# MainBoardR6.net
KiCad netlist of a schematic drawn in EAGLE
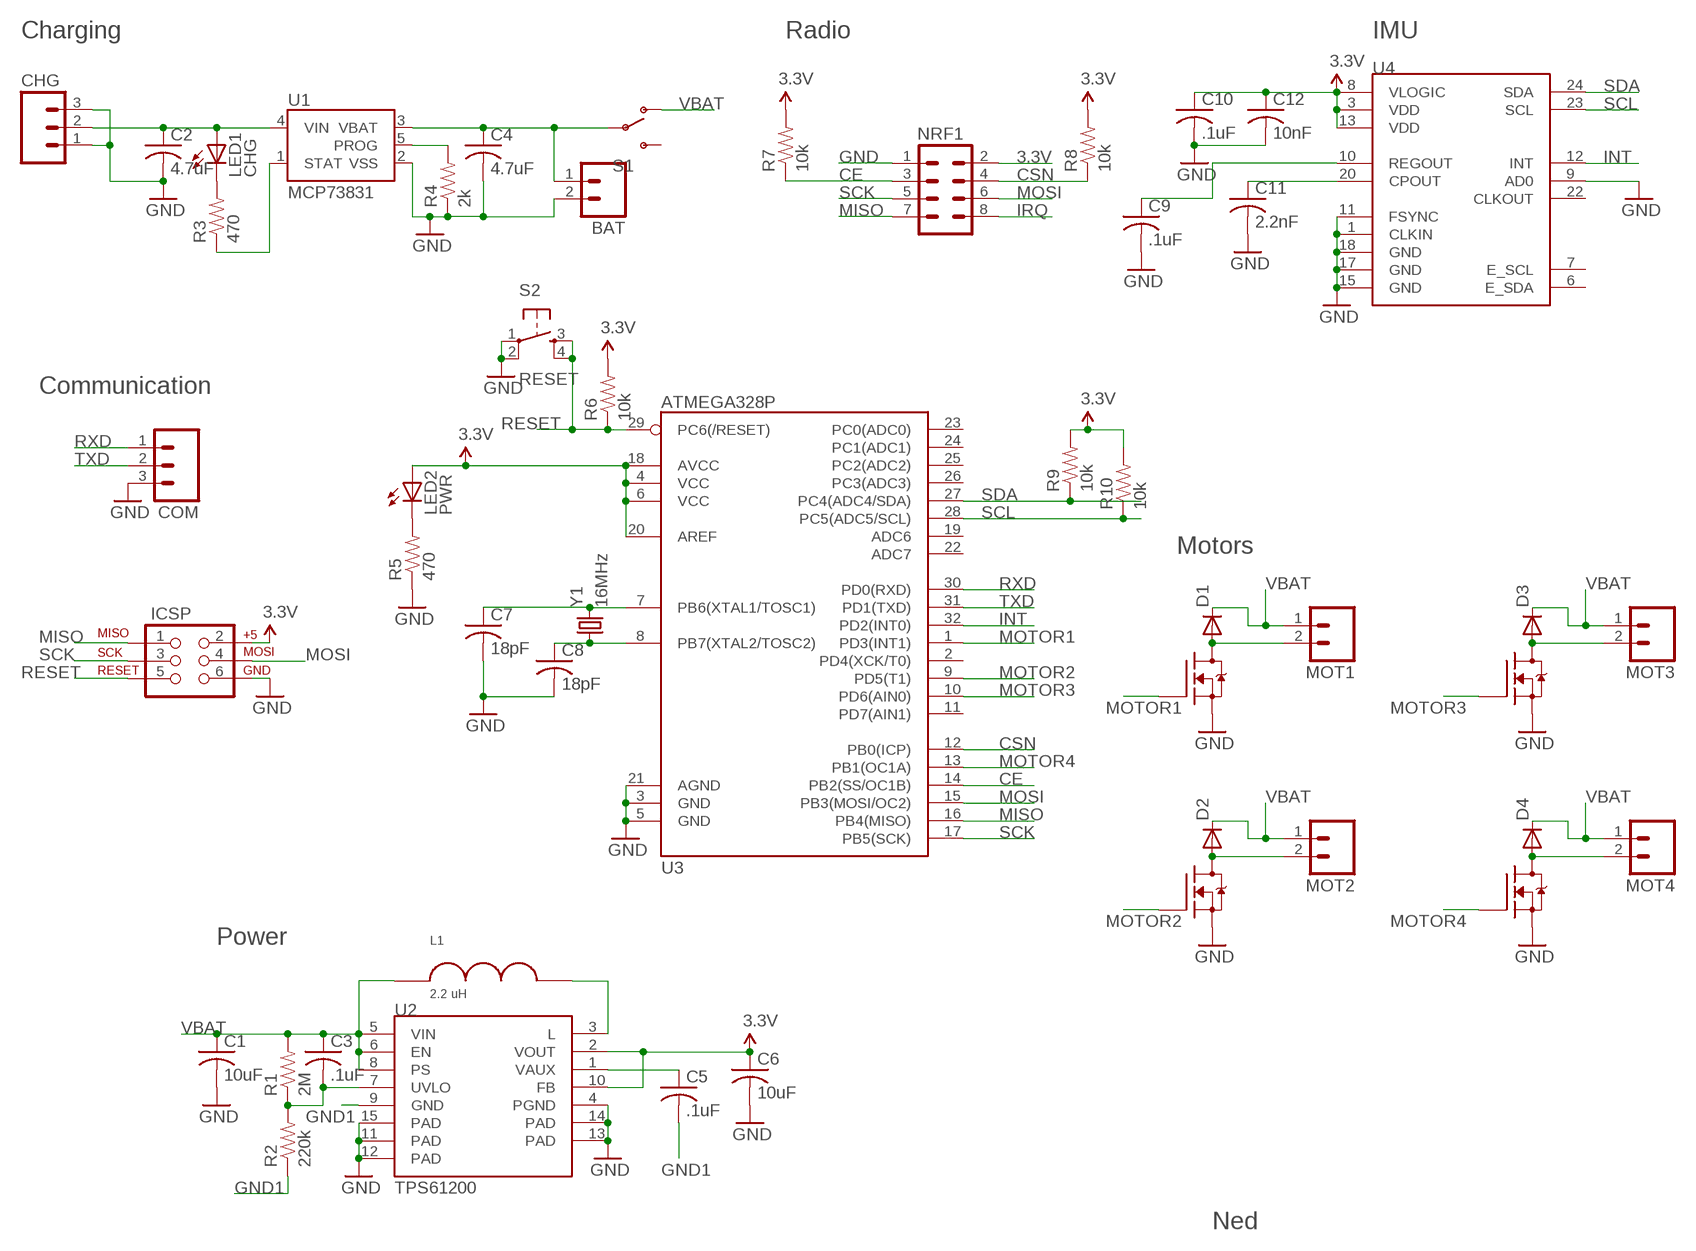
[diagram p0: schematic, sheet 1]

(export (version "E")
  (design (tool "Eeschema 10.0.6"))
  (components
    (comp (ref "BAT")
      (value "M02LOCK_LONGPADS")
      (footprint "eagle-import:1X02_LOCK_LONGPADS")
      (libsource (lib "eagle-import") (part "M02LOCK_LONGPADS"))
    )
    (comp (ref "C1")
      (value "10uF")
      (footprint "eagle-import:C0805")
      (libsource (lib "eagle-import") (part "C-USC0805"))
    )
    (comp (ref "C2")
      (value "4.7uF")
      (footprint "eagle-import:C0805")
      (libsource (lib "eagle-import") (part "C-USC0805"))
    )
    (comp (ref "C3")
      (value ".1uF")
      (footprint "eagle-import:C0805")
      (libsource (lib "eagle-import") (part "C-USC0805"))
    )
    (comp (ref "C4")
      (value "4.7uF")
      (footprint "eagle-import:C0805")
      (libsource (lib "eagle-import") (part "C-USC0805"))
    )
    (comp (ref "C5")
      (value ".1uF")
      (footprint "eagle-import:C0805")
      (libsource (lib "eagle-import") (part "C-USC0805"))
    )
    (comp (ref "C6")
      (value "10uF")
      (footprint "eagle-import:C0805")
      (libsource (lib "eagle-import") (part "C-USC0805"))
    )
    (comp (ref "C7")
      (value "18pF")
      (footprint "eagle-import:C0805")
      (libsource (lib "eagle-import") (part "C-USC0805"))
    )
    (comp (ref "C8")
      (value "18pF")
      (footprint "eagle-import:C0805")
      (libsource (lib "eagle-import") (part "C-USC0805"))
    )
    (comp (ref "C9")
      (value ".1uF")
      (footprint "eagle-import:C0805")
      (libsource (lib "eagle-import") (part "C-USC0805"))
    )
    (comp (ref "C10")
      (value ".1uF")
      (footprint "eagle-import:C0805")
      (libsource (lib "eagle-import") (part "C-USC0805"))
    )
    (comp (ref "C11")
      (value "2.2nF")
      (footprint "eagle-import:C0805")
      (libsource (lib "eagle-import") (part "C-USC0805"))
    )
    (comp (ref "C12")
      (value "10nF")
      (footprint "eagle-import:C0805")
      (libsource (lib "eagle-import") (part "C-USC0805"))
    )
    (comp (ref "CHG")
      (value "M03LONGPADS")
      (footprint "eagle-import:1X03_LONGPADS")
      (libsource (lib "eagle-import") (part "M03LONGPADS"))
    )
    (comp (ref "COM")
      (value "M03LONGPADS")
      (footprint "eagle-import:1X03_LONGPADS")
      (libsource (lib "eagle-import") (part "M03LONGPADS"))
    )
    (comp (ref "D1")
      (value "BAS16-V-GS18")
      (footprint "eagle-import:SOT23")
      (libsource (lib "eagle-import") (part "BAS16-V-GS18"))
    )
    (comp (ref "D2")
      (value "BAS16-V-GS18")
      (footprint "eagle-import:SOT23")
      (libsource (lib "eagle-import") (part "BAS16-V-GS18"))
    )
    (comp (ref "D3")
      (value "BAS16-V-GS18")
      (footprint "eagle-import:SOT23")
      (libsource (lib "eagle-import") (part "BAS16-V-GS18"))
    )
    (comp (ref "D4")
      (value "BAS16-V-GS18")
      (footprint "eagle-import:SOT23")
      (libsource (lib "eagle-import") (part "BAS16-V-GS18"))
    )
    (comp (ref "ICSP")
      (value "AVR_SPI_PRG_62X3_LOCK")
      (footprint "eagle-import:2X3_LOCK")
      (libsource (lib "eagle-import") (part "AVR_SPI_PRG_62X3_LOCK"))
    )
    (comp (ref "L1")
      (value "2.2 uH")
      (footprint "eagle-import:2518")
      (libsource (lib "eagle-import") (part "BRHL2518T2R2M"))
    )
    (comp (ref "LED1")
      (value "CHG")
      (footprint "eagle-import:LED-1206")
      (libsource (lib "eagle-import") (part "LED1206"))
    )
    (comp (ref "LED2")
      (value "PWR")
      (footprint "eagle-import:LED-1206")
      (libsource (lib "eagle-import") (part "LED1206"))
    )
    (comp (ref "MOT1")
      (value "M02LOCK_LONGPADS")
      (footprint "eagle-import:1X02_LOCK_LONGPADS")
      (libsource (lib "eagle-import") (part "M02LOCK_LONGPADS"))
    )
    (comp (ref "MOT2")
      (value "M02LOCK_LONGPADS")
      (footprint "eagle-import:1X02_LOCK_LONGPADS")
      (libsource (lib "eagle-import") (part "M02LOCK_LONGPADS"))
    )
    (comp (ref "MOT3")
      (value "M02LOCK_LONGPADS")
      (footprint "eagle-import:1X02_LOCK_LONGPADS")
      (libsource (lib "eagle-import") (part "M02LOCK_LONGPADS"))
    )
    (comp (ref "MOT4")
      (value "M02LOCK_LONGPADS")
      (footprint "eagle-import:1X02_LOCK_LONGPADS")
      (libsource (lib "eagle-import") (part "M02LOCK_LONGPADS"))
    )
    (comp (ref "NRF1")
      (value "M04X2")
      (footprint "eagle-import:2X4")
      (libsource (lib "eagle-import") (part "M04X2"))
    )
    (comp (ref "R1")
      (value "2M")
      (footprint "eagle-import:0805")
      (libsource (lib "eagle-import") (part "RESISTOR0805-RES"))
    )
    (comp (ref "R2")
      (value "220k")
      (footprint "eagle-import:0805")
      (libsource (lib "eagle-import") (part "RESISTOR0805-RES"))
    )
    (comp (ref "R3")
      (value "470")
      (footprint "eagle-import:0805")
      (libsource (lib "eagle-import") (part "RESISTOR0805-RES"))
    )
    (comp (ref "R4")
      (value "2k")
      (footprint "eagle-import:0805")
      (libsource (lib "eagle-import") (part "RESISTOR0805-RES"))
    )
    (comp (ref "R5")
      (value "470")
      (footprint "eagle-import:0805")
      (libsource (lib "eagle-import") (part "RESISTOR0805-RES"))
    )
    (comp (ref "R6")
      (value "10k")
      (footprint "eagle-import:0805")
      (libsource (lib "eagle-import") (part "RESISTOR0805-RES"))
    )
    (comp (ref "R7")
      (value "10k")
      (footprint "eagle-import:0805")
      (libsource (lib "eagle-import") (part "RESISTOR0805-RES"))
    )
    (comp (ref "R8")
      (value "10k")
      (footprint "eagle-import:0805")
      (libsource (lib "eagle-import") (part "RESISTOR0805-RES"))
    )
    (comp (ref "R9")
      (value "10k")
      (footprint "eagle-import:0805")
      (libsource (lib "eagle-import") (part "RESISTOR0805-RES"))
    )
    (comp (ref "R10")
      (value "10k")
      (footprint "eagle-import:0805")
      (libsource (lib "eagle-import") (part "RESISTOR0805-RES"))
    )
    (comp (ref "S1")
      (value "SWITCH-SPST-SMD-A")
      (footprint "eagle-import:SWITCH-SPST-SMD-A")
      (libsource (lib "eagle-import") (part "SWITCH-SPST-SMD-A"))
    )
    (comp (ref "S2")
      (value "RESET")
      (footprint "eagle-import:TACTILE_SWITCH_SMD")
      (libsource (lib "eagle-import") (part "TAC_SWITCHSMD"))
    )
    (comp (ref "T1")
      (value "SI1902CDL")
      (footprint "eagle-import:SOT363_INFINEON")
      (libsource (lib "eagle-import") (part "SI1902CDL"))
    )
    (comp (ref "T2")
      (value "SI1902CDL")
      (footprint "eagle-import:SOT363_INFINEON")
      (libsource (lib "eagle-import") (part "SI1902CDL"))
    )
    (comp (ref "U1")
      (value "MCP73831")
      (footprint "eagle-import:SOT23-5")
      (libsource (lib "eagle-import") (part "MCP73831"))
    )
    (comp (ref "U2")
      (value "TPS61200")
      (footprint "eagle-import:QFN-10_PAD")
      (libsource (lib "eagle-import") (part "TPS61200"))
    )
    (comp (ref "U3")
      (value "ATMEGA328P")
      (footprint "eagle-import:TQFP32-08")
      (libsource (lib "eagle-import") (part "ATMEGA328_SMT"))
    )
    (comp (ref "U4")
      (value "MPU-9150QFN-24-NP")
      (footprint "eagle-import:QFN-24-NP")
      (libsource (lib "eagle-import") (part "MPU-9150QFN-24-NP"))
    )
    (comp (ref "Y1")
      (value "16MHz")
      (footprint "eagle-import:CRYSTAL-SMD-5X3")
      (libsource (lib "eagle-import") (part "CRYSTAL5X3"))
    )
  )
  (nets
    (net (code "1") (name "/CE") (class "Default")
      (node (ref "NRF1") (pin "3") (pinfunction "3_3") (pintype "passive"))
      (node (ref "R7") (pin "1") (pinfunction "1_1") (pintype "passive"))
      (node (ref "U3") (pin "14") (pinfunction "PB2(SS/OC1B)_14") (pintype "bidirectional"))
    )
    (net (code "2") (name "/CSN") (class "Default")
      (node (ref "NRF1") (pin "4") (pinfunction "4_4") (pintype "passive"))
      (node (ref "R8") (pin "1") (pinfunction "1_1") (pintype "passive"))
      (node (ref "U3") (pin "12") (pinfunction "PB0(ICP)_12") (pintype "bidirectional"))
    )
    (net (code "3") (name "/GND1") (class "Default")
      (node (ref "C5") (pin "2") (pinfunction "2_2") (pintype "passive"))
      (node (ref "R2") (pin "1") (pinfunction "1_1") (pintype "passive"))
      (node (ref "U2") (pin "9") (pinfunction "GND_9") (pintype "power_in"))
    )
    (net (code "4") (name "/INT") (class "Default")
      (node (ref "U3") (pin "32") (pinfunction "PD2(INT0)_32") (pintype "bidirectional"))
      (node (ref "U4") (pin "12") (pinfunction "INT_12") (pintype "bidirectional"))
    )
    (net (code "5") (name "/IRQ") (class "Default")
      (node (ref "NRF1") (pin "8") (pinfunction "8_8") (pintype "passive"))
    )
    (net (code "6") (name "/MISO") (class "Default")
      (node (ref "ICSP") (pin "1") (pinfunction "1_1") (pintype "passive"))
      (node (ref "NRF1") (pin "7") (pinfunction "7_7") (pintype "passive"))
      (node (ref "U3") (pin "16") (pinfunction "PB4(MISO)_16") (pintype "bidirectional"))
    )
    (net (code "7") (name "/MOSI") (class "Default")
      (node (ref "ICSP") (pin "4") (pinfunction "4_4") (pintype "passive"))
      (node (ref "NRF1") (pin "6") (pinfunction "6_6") (pintype "passive"))
      (node (ref "U3") (pin "15") (pinfunction "PB3(MOSI/OC2)_15") (pintype "bidirectional"))
    )
    (net (code "8") (name "/MOTOR1") (class "Default")
      (node (ref "T1") (pin "2") (pinfunction "G_2") (pintype "passive"))
      (node (ref "U3") (pin "1") (pinfunction "PD3(INT1)_1") (pintype "bidirectional"))
    )
    (net (code "9") (name "/MOTOR2") (class "Default")
      (node (ref "T1") (pin "5") (pinfunction "G_5") (pintype "passive"))
      (node (ref "U3") (pin "9") (pinfunction "PD5(T1)_9") (pintype "bidirectional"))
    )
    (net (code "10") (name "/MOTOR3") (class "Default")
      (node (ref "T2") (pin "2") (pinfunction "G_2") (pintype "passive"))
      (node (ref "U3") (pin "10") (pinfunction "PD6(AIN0)_10") (pintype "bidirectional"))
    )
    (net (code "11") (name "/MOTOR4") (class "Default")
      (node (ref "T2") (pin "5") (pinfunction "G_5") (pintype "passive"))
      (node (ref "U3") (pin "13") (pinfunction "PB1(OC1A)_13") (pintype "bidirectional"))
    )
    (net (code "12") (name "/RESET") (class "Default")
      (node (ref "ICSP") (pin "5") (pinfunction "5_5") (pintype "passive"))
      (node (ref "R6") (pin "1") (pinfunction "1_1") (pintype "passive"))
      (node (ref "S2") (pin "3") (pinfunction "3_3") (pintype "passive"))
      (node (ref "S2") (pin "4") (pinfunction "4_4") (pintype "passive"))
      (node (ref "U3") (pin "29") (pinfunction "PC6(/RESET)_29") (pintype "bidirectional"))
    )
    (net (code "13") (name "/RXD") (class "Default")
      (node (ref "COM") (pin "1") (pinfunction "1_1") (pintype "passive"))
      (node (ref "U3") (pin "30") (pinfunction "PD0(RXD)_30") (pintype "bidirectional"))
    )
    (net (code "14") (name "/SCK") (class "Default")
      (node (ref "ICSP") (pin "3") (pinfunction "3_3") (pintype "passive"))
      (node (ref "NRF1") (pin "5") (pinfunction "5_5") (pintype "passive"))
      (node (ref "U3") (pin "17") (pinfunction "PB5(SCK)_17") (pintype "bidirectional"))
    )
    (net (code "15") (name "/SCL") (class "Default")
      (node (ref "R10") (pin "1") (pinfunction "1_1") (pintype "passive"))
      (node (ref "U3") (pin "28") (pinfunction "PC5(ADC5/SCL)_28") (pintype "bidirectional"))
      (node (ref "U4") (pin "23") (pinfunction "SCL_23") (pintype "bidirectional"))
    )
    (net (code "16") (name "/SDA") (class "Default")
      (node (ref "R9") (pin "1") (pinfunction "1_1") (pintype "passive"))
      (node (ref "U3") (pin "27") (pinfunction "PC4(ADC4/SDA)_27") (pintype "bidirectional"))
      (node (ref "U4") (pin "24") (pinfunction "SDA_24") (pintype "bidirectional"))
    )
    (net (code "17") (name "/TXD") (class "Default")
      (node (ref "COM") (pin "2") (pinfunction "2_2") (pintype "passive"))
      (node (ref "U3") (pin "31") (pinfunction "PD1(TXD)_31") (pintype "bidirectional"))
    )
    (net (code "18") (name "/VBAT") (class "Default")
      (node (ref "C1") (pin "1") (pinfunction "1_1") (pintype "passive"))
      (node (ref "C3") (pin "1") (pinfunction "1_1") (pintype "passive"))
      (node (ref "D1") (pin "3") (pinfunction "C_3") (pintype "passive"))
      (node (ref "D2") (pin "3") (pinfunction "C_3") (pintype "passive"))
      (node (ref "D3") (pin "3") (pinfunction "C_3") (pintype "passive"))
      (node (ref "D4") (pin "3") (pinfunction "C_3") (pintype "passive"))
      (node (ref "L1") (pin "P$1") (pinfunction "1_P$1") (pintype "bidirectional"))
      (node (ref "MOT1") (pin "1") (pinfunction "1_1") (pintype "passive"))
      (node (ref "MOT2") (pin "1") (pinfunction "1_1") (pintype "passive"))
      (node (ref "MOT3") (pin "1") (pinfunction "1_1") (pintype "passive"))
      (node (ref "MOT4") (pin "1") (pinfunction "1_1") (pintype "passive"))
      (node (ref "R1") (pin "2") (pinfunction "2_2") (pintype "passive"))
      (node (ref "S1") (pin "1") (pinfunction "O_1") (pintype "passive"))
      (node (ref "U2") (pin "5") (pinfunction "VIN_5") (pintype "power_in"))
      (node (ref "U2") (pin "6") (pinfunction "EN_6") (pintype "input"))
      (node (ref "U2") (pin "8") (pinfunction "PS_8") (pintype "input"))
    )
    (net (code "19") (name "3.3V") (class "Default")
      (node (ref "C10") (pin "1") (pinfunction "1_1") (pintype "passive"))
      (node (ref "C12") (pin "1") (pinfunction "1_1") (pintype "passive"))
      (node (ref "C6") (pin "1") (pinfunction "1_1") (pintype "passive"))
      (node (ref "ICSP") (pin "2") (pinfunction "2_2") (pintype "passive"))
      (node (ref "LED2") (pin "A") (pinfunction "A_A") (pintype "passive"))
      (node (ref "NRF1") (pin "2") (pinfunction "2_2") (pintype "passive"))
      (node (ref "R10") (pin "2") (pinfunction "2_2") (pintype "passive"))
      (node (ref "R6") (pin "2") (pinfunction "2_2") (pintype "passive"))
      (node (ref "R7") (pin "2") (pinfunction "2_2") (pintype "passive"))
      (node (ref "R8") (pin "2") (pinfunction "2_2") (pintype "passive"))
      (node (ref "R9") (pin "2") (pinfunction "2_2") (pintype "passive"))
      (node (ref "U2") (pin "10") (pinfunction "FB_10") (pintype "passive"))
      (node (ref "U2") (pin "2") (pinfunction "VOUT_2") (pintype "passive"))
      (node (ref "U3") (pin "18") (pinfunction "AVCC_18") (pintype "bidirectional"))
      (node (ref "U3") (pin "20") (pinfunction "AREF_20") (pintype "bidirectional"))
      (node (ref "U3") (pin "4") (pinfunction "VCC_4") (pintype "bidirectional"))
      (node (ref "U3") (pin "6") (pinfunction "VCC_6") (pintype "bidirectional"))
      (node (ref "U4") (pin "13") (pinfunction "VDD_13") (pintype "bidirectional"))
      (node (ref "U4") (pin "3") (pinfunction "VDD_3") (pintype "bidirectional"))
      (node (ref "U4") (pin "8") (pinfunction "VLOGIC_8") (pintype "bidirectional"))
    )
    (net (code "20") (name "GND") (class "Default")
      (node (ref "BAT") (pin "2") (pinfunction "2_2") (pintype "passive"))
      (node (ref "C1") (pin "2") (pinfunction "2_2") (pintype "passive"))
      (node (ref "C10") (pin "2") (pinfunction "2_2") (pintype "passive"))
      (node (ref "C11") (pin "2") (pinfunction "2_2") (pintype "passive"))
      (node (ref "C12") (pin "2") (pinfunction "2_2") (pintype "passive"))
      (node (ref "C2") (pin "2") (pinfunction "2_2") (pintype "passive"))
      (node (ref "C4") (pin "2") (pinfunction "2_2") (pintype "passive"))
      (node (ref "C6") (pin "2") (pinfunction "2_2") (pintype "passive"))
      (node (ref "C7") (pin "2") (pinfunction "2_2") (pintype "passive"))
      (node (ref "C8") (pin "2") (pinfunction "2_2") (pintype "passive"))
      (node (ref "C9") (pin "2") (pinfunction "2_2") (pintype "passive"))
      (node (ref "CHG") (pin "1") (pinfunction "1_1") (pintype "passive"))
      (node (ref "CHG") (pin "3") (pinfunction "3_3") (pintype "passive"))
      (node (ref "COM") (pin "3") (pinfunction "3_3") (pintype "passive"))
      (node (ref "ICSP") (pin "6") (pinfunction "6_6") (pintype "passive"))
      (node (ref "NRF1") (pin "1") (pinfunction "1_1") (pintype "passive"))
      (node (ref "R4") (pin "1") (pinfunction "1_1") (pintype "passive"))
      (node (ref "R5") (pin "1") (pinfunction "1_1") (pintype "passive"))
      (node (ref "S2") (pin "1") (pinfunction "1_1") (pintype "passive"))
      (node (ref "S2") (pin "2") (pinfunction "2_2") (pintype "passive"))
      (node (ref "T1") (pin "1") (pinfunction "S_1") (pintype "passive"))
      (node (ref "T1") (pin "4") (pinfunction "S_4") (pintype "passive"))
      (node (ref "T2") (pin "1") (pinfunction "S_1") (pintype "passive"))
      (node (ref "T2") (pin "4") (pinfunction "S_4") (pintype "passive"))
      (node (ref "U1") (pin "2") (pinfunction "VSS_2") (pintype "power_in"))
      (node (ref "U2") (pin "11") (pinfunction "PAD_11") (pintype "power_in"))
      (node (ref "U2") (pin "12") (pinfunction "PAD_12") (pintype "power_in"))
      (node (ref "U2") (pin "13") (pinfunction "PAD_13") (pintype "power_in"))
      (node (ref "U2") (pin "14") (pinfunction "PAD_14") (pintype "power_in"))
      (node (ref "U2") (pin "15") (pinfunction "PAD_15") (pintype "power_in"))
      (node (ref "U2") (pin "4") (pinfunction "PGND_4") (pintype "power_in"))
      (node (ref "U3") (pin "21") (pinfunction "AGND_21") (pintype "bidirectional"))
      (node (ref "U3") (pin "3") (pinfunction "GND_3") (pintype "bidirectional"))
      (node (ref "U3") (pin "5") (pinfunction "GND_5") (pintype "bidirectional"))
      (node (ref "U4") (pin "1") (pinfunction "CLKIN_1") (pintype "bidirectional"))
      (node (ref "U4") (pin "11") (pinfunction "FSYNC_11") (pintype "bidirectional"))
      (node (ref "U4") (pin "15") (pinfunction "GND_15") (pintype "bidirectional"))
      (node (ref "U4") (pin "17") (pinfunction "GND_17") (pintype "bidirectional"))
      (node (ref "U4") (pin "18") (pinfunction "GND_18") (pintype "bidirectional"))
      (node (ref "U4") (pin "9") (pinfunction "AD0_9") (pintype "bidirectional"))
    )
    (net (code "21") (name "Net-(D1-A)") (class "Default")
      (node (ref "D1") (pin "1") (pinfunction "A_1") (pintype "passive"))
      (node (ref "MOT1") (pin "2") (pinfunction "2_2") (pintype "passive"))
      (node (ref "T1") (pin "6") (pinfunction "D_6") (pintype "passive"))
    )
    (net (code "22") (name "Net-(D2-A)") (class "Default")
      (node (ref "D2") (pin "1") (pinfunction "A_1") (pintype "passive"))
      (node (ref "MOT2") (pin "2") (pinfunction "2_2") (pintype "passive"))
      (node (ref "T1") (pin "3") (pinfunction "D_3") (pintype "passive"))
    )
    (net (code "23") (name "Net-(D3-A)") (class "Default")
      (node (ref "D3") (pin "1") (pinfunction "A_1") (pintype "passive"))
      (node (ref "MOT3") (pin "2") (pinfunction "2_2") (pintype "passive"))
      (node (ref "T2") (pin "6") (pinfunction "D_6") (pintype "passive"))
    )
    (net (code "24") (name "Net-(D4-A)") (class "Default")
      (node (ref "D4") (pin "1") (pinfunction "A_1") (pintype "passive"))
      (node (ref "MOT4") (pin "2") (pinfunction "2_2") (pintype "passive"))
      (node (ref "T2") (pin "3") (pinfunction "D_3") (pintype "passive"))
    )
    (net (code "25") (name "Net-(L1-2)") (class "Default")
      (node (ref "L1") (pin "P$2") (pinfunction "2_P$2") (pintype "bidirectional"))
      (node (ref "U2") (pin "3") (pinfunction "L_3") (pintype "passive"))
    )
    (net (code "26") (name "Net-(LED1-PadC)") (class "Default")
      (node (ref "LED1") (pin "C") (pinfunction "C_C") (pintype "passive"))
      (node (ref "R3") (pin "2") (pinfunction "2_2") (pintype "passive"))
    )
    (net (code "27") (name "Net-(LED2-PadC)") (class "Default")
      (node (ref "LED2") (pin "C") (pinfunction "C_C") (pintype "passive"))
      (node (ref "R5") (pin "2") (pinfunction "2_2") (pintype "passive"))
    )
    (net (code "28") (name "Net-(S1-P)") (class "Default")
      (node (ref "BAT") (pin "1") (pinfunction "1_1") (pintype "passive"))
      (node (ref "C4") (pin "1") (pinfunction "1_1") (pintype "passive"))
      (node (ref "S1") (pin "2") (pinfunction "P_2") (pintype "passive"))
      (node (ref "U1") (pin "3") (pinfunction "VBAT_3") (pintype "power_in"))
    )
    (net (code "29") (name "Net-(U1-PROG)") (class "Default")
      (node (ref "R4") (pin "2") (pinfunction "2_2") (pintype "passive"))
      (node (ref "U1") (pin "5") (pinfunction "PROG_5") (pintype "input"))
    )
    (net (code "30") (name "Net-(U1-STAT)") (class "Default")
      (node (ref "R3") (pin "1") (pinfunction "1_1") (pintype "passive"))
      (node (ref "U1") (pin "1") (pinfunction "STAT_1") (pintype "output"))
    )
    (net (code "31") (name "Net-(U1-VIN)") (class "Default")
      (node (ref "C2") (pin "1") (pinfunction "1_1") (pintype "passive"))
      (node (ref "CHG") (pin "2") (pinfunction "2_2") (pintype "passive"))
      (node (ref "LED1") (pin "A") (pinfunction "A_A") (pintype "passive"))
      (node (ref "U1") (pin "4") (pinfunction "VIN_4") (pintype "power_in"))
    )
    (net (code "32") (name "Net-(U2-UVLO)") (class "Default")
      (node (ref "C3") (pin "2") (pinfunction "2_2") (pintype "passive"))
      (node (ref "R1") (pin "1") (pinfunction "1_1") (pintype "passive"))
      (node (ref "R2") (pin "2") (pinfunction "2_2") (pintype "passive"))
      (node (ref "U2") (pin "7") (pinfunction "UVLO_7") (pintype "passive"))
    )
    (net (code "33") (name "Net-(U2-VAUX)") (class "Default")
      (node (ref "C5") (pin "1") (pinfunction "1_1") (pintype "passive"))
      (node (ref "U2") (pin "1") (pinfunction "VAUX_1") (pintype "passive"))
    )
    (net (code "34") (name "Net-(U3-PB6(XTAL1{slash}TOSC1))") (class "Default")
      (node (ref "C7") (pin "1") (pinfunction "1_1") (pintype "passive"))
      (node (ref "U3") (pin "7") (pinfunction "PB6(XTAL1/TOSC1)_7") (pintype "bidirectional"))
      (node (ref "Y1") (pin "3") (pinfunction "2_3") (pintype "passive"))
    )
    (net (code "35") (name "Net-(U3-PB7(XTAL2{slash}TOSC2))") (class "Default")
      (node (ref "C8") (pin "1") (pinfunction "1_1") (pintype "passive"))
      (node (ref "U3") (pin "8") (pinfunction "PB7(XTAL2/TOSC2)_8") (pintype "bidirectional"))
      (node (ref "Y1") (pin "1") (pinfunction "1_1") (pintype "passive"))
    )
    (net (code "36") (name "Net-(U4-CPOUT)") (class "Default")
      (node (ref "C11") (pin "1") (pinfunction "1_1") (pintype "passive"))
      (node (ref "U4") (pin "20") (pinfunction "CPOUT_20") (pintype "bidirectional"))
    )
    (net (code "37") (name "Net-(U4-REGOUT)") (class "Default")
      (node (ref "C9") (pin "1") (pinfunction "1_1") (pintype "passive"))
      (node (ref "U4") (pin "10") (pinfunction "REGOUT_10") (pintype "bidirectional"))
    )
    (net (code "38") (name "unconnected-(S1-S-Pad3)") (class "Default")
      (node (ref "S1") (pin "3") (pinfunction "S_3") (pintype "passive"))
    )
    (net (code "39") (name "unconnected-(U3-ADC6-Pad19)") (class "Default")
      (node (ref "U3") (pin "19") (pinfunction "ADC6_19") (pintype "bidirectional"))
    )
    (net (code "40") (name "unconnected-(U3-ADC7-Pad22)") (class "Default")
      (node (ref "U3") (pin "22") (pinfunction "ADC7_22") (pintype "bidirectional"))
    )
    (net (code "41") (name "unconnected-(U3-PC0(ADC0)-Pad23)") (class "Default")
      (node (ref "U3") (pin "23") (pinfunction "PC0(ADC0)_23") (pintype "bidirectional"))
    )
    (net (code "42") (name "unconnected-(U3-PC1(ADC1)-Pad24)") (class "Default")
      (node (ref "U3") (pin "24") (pinfunction "PC1(ADC1)_24") (pintype "bidirectional"))
    )
    (net (code "43") (name "unconnected-(U3-PC2(ADC2)-Pad25)") (class "Default")
      (node (ref "U3") (pin "25") (pinfunction "PC2(ADC2)_25") (pintype "bidirectional"))
    )
    (net (code "44") (name "unconnected-(U3-PC3(ADC3)-Pad26)") (class "Default")
      (node (ref "U3") (pin "26") (pinfunction "PC3(ADC3)_26") (pintype "bidirectional"))
    )
    (net (code "45") (name "unconnected-(U3-PD4(XCK{slash}T0)-Pad2)") (class "Default")
      (node (ref "U3") (pin "2") (pinfunction "PD4(XCK/T0)_2") (pintype "bidirectional"))
    )
    (net (code "46") (name "unconnected-(U3-PD7(AIN1)-Pad11)") (class "Default")
      (node (ref "U3") (pin "11") (pinfunction "PD7(AIN1)_11") (pintype "bidirectional"))
    )
    (net (code "47") (name "unconnected-(U4-CLKOUT-Pad22)") (class "Default")
      (node (ref "U4") (pin "22") (pinfunction "CLKOUT_22") (pintype "bidirectional"))
    )
    (net (code "48") (name "unconnected-(U4-E_SCL-Pad7)") (class "Default")
      (node (ref "U4") (pin "7") (pinfunction "E_SCL_7") (pintype "bidirectional"))
    )
    (net (code "49") (name "unconnected-(U4-E_SDA-Pad6)") (class "Default")
      (node (ref "U4") (pin "6") (pinfunction "E_SDA_6") (pintype "bidirectional"))
    )
  )
)
